# EN-C200_RA0_MCU.net
KiCad netlist of a schematic drawn in Altium Designer
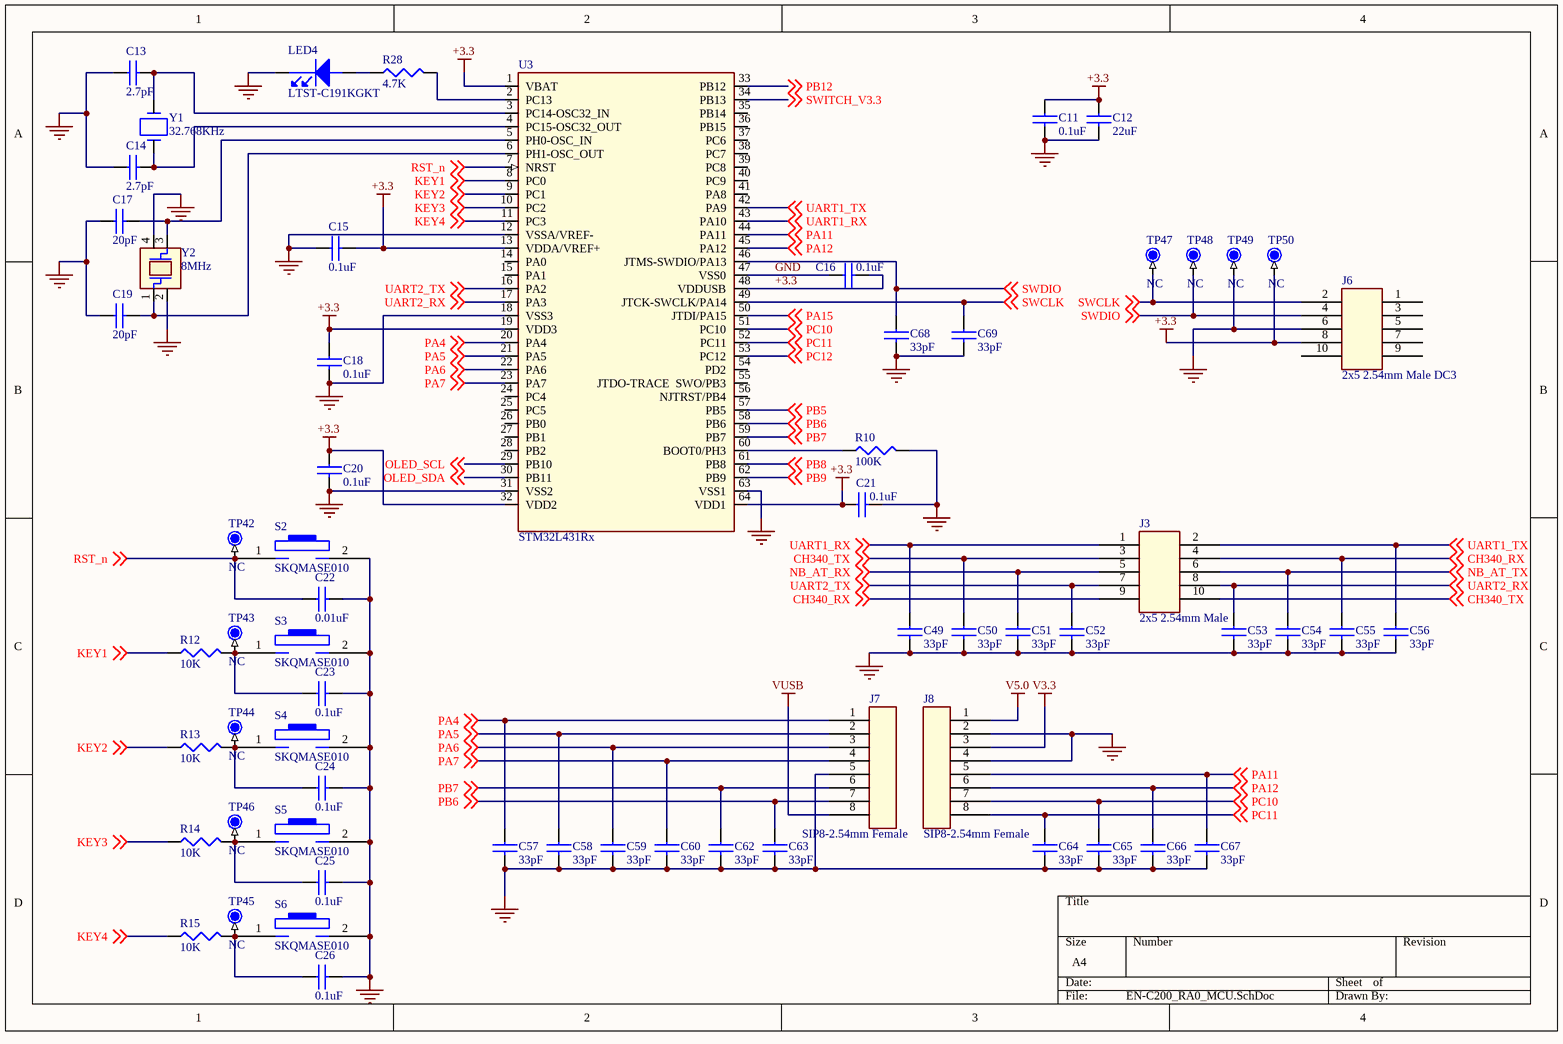
[diagram p0: EN-C200_RA0_MCU.SchDoc]

(export (version "E")
  (design (tool "Eeschema 10.0.6"))
  (components
    (comp (ref "C11") (value "0.1uF") (footprint "SC0603") (libsource (lib "EN-C200_RA0") (part "CAP NP")))
    (comp (ref "C12") (value "22uF") (footprint "SC0805") (libsource (lib "EN-C200_RA0") (part "CAP NP")))
    (comp (ref "C13") (value "2.7pF") (footprint "SC0603") (libsource (lib "EN-C200_RA0") (part "CAP NP")))
    (comp (ref "C14") (value "2.7pF") (footprint "SC0603") (libsource (lib "EN-C200_RA0") (part "CAP NP")))
    (comp (ref "C15") (value "0.1uF") (footprint "SC0603") (libsource (lib "EN-C200_RA0") (part "CAP NP")))
    (comp (ref "C16") (value "0.1uF") (footprint "SC0603") (libsource (lib "EN-C200_RA0") (part "CAP NP")))
    (comp (ref "C17") (value "20pF") (footprint "SC0603") (libsource (lib "EN-C200_RA0") (part "CAP NP")))
    (comp (ref "C18") (value "0.1uF") (footprint "SC0603") (libsource (lib "EN-C200_RA0") (part "CAP NP")))
    (comp (ref "C19") (value "20pF") (footprint "SC0603") (libsource (lib "EN-C200_RA0") (part "CAP NP")))
    (comp (ref "C20") (value "0.1uF") (footprint "SC0603") (libsource (lib "EN-C200_RA0") (part "CAP NP")))
    (comp (ref "C21") (value "0.1uF") (footprint "SC0603") (libsource (lib "EN-C200_RA0") (part "CAP NP")))
    (comp (ref "C22") (value "0.01uF") (footprint "SC0603") (libsource (lib "EN-C200_RA0") (part "CAP NP")))
    (comp (ref "C23") (value "0.1uF") (footprint "SC0603") (libsource (lib "EN-C200_RA0") (part "CAP NP")))
    (comp (ref "C24") (value "0.1uF") (footprint "SC0603") (libsource (lib "EN-C200_RA0") (part "CAP NP")))
    (comp (ref "C25") (value "0.1uF") (footprint "SC0603") (libsource (lib "EN-C200_RA0") (part "CAP NP")))
    (comp (ref "C26") (value "0.1uF") (footprint "SC0603") (libsource (lib "EN-C200_RA0") (part "CAP NP")))
    (comp (ref "C49") (value "33pF") (footprint "SC0603") (libsource (lib "EN-C200_RA0") (part "CAP NP")))
    (comp (ref "C50") (value "33pF") (footprint "SC0603") (libsource (lib "EN-C200_RA0") (part "CAP NP")))
    (comp (ref "C51") (value "33pF") (footprint "SC0603") (libsource (lib "EN-C200_RA0") (part "CAP NP")))
    (comp (ref "C52") (value "33pF") (footprint "SC0603") (libsource (lib "EN-C200_RA0") (part "CAP NP")))
    (comp (ref "C53") (value "33pF") (footprint "SC0603") (libsource (lib "EN-C200_RA0") (part "CAP NP")))
    (comp (ref "C54") (value "33pF") (footprint "SC0603") (libsource (lib "EN-C200_RA0") (part "CAP NP")))
    (comp (ref "C55") (value "33pF") (footprint "SC0603") (libsource (lib "EN-C200_RA0") (part "CAP NP")))
    (comp (ref "C56") (value "33pF") (footprint "SC0603") (libsource (lib "EN-C200_RA0") (part "CAP NP")))
    (comp (ref "C57") (value "33pF") (footprint "SC0603") (libsource (lib "EN-C200_RA0") (part "CAP NP")))
    (comp (ref "C58") (value "33pF") (footprint "SC0603") (libsource (lib "EN-C200_RA0") (part "CAP NP")))
    (comp (ref "C59") (value "33pF") (footprint "SC0603") (libsource (lib "EN-C200_RA0") (part "CAP NP")))
    (comp (ref "C60") (value "33pF") (footprint "SC0603") (libsource (lib "EN-C200_RA0") (part "CAP NP")))
    (comp (ref "C62") (value "33pF") (footprint "SC0603") (libsource (lib "EN-C200_RA0") (part "CAP NP")))
    (comp (ref "C63") (value "33pF") (footprint "SC0603") (libsource (lib "EN-C200_RA0") (part "CAP NP")))
    (comp (ref "C64") (value "33pF") (footprint "SC0603") (libsource (lib "EN-C200_RA0") (part "CAP NP")))
    (comp (ref "C65") (value "33pF") (footprint "SC0603") (libsource (lib "EN-C200_RA0") (part "CAP NP")))
    (comp (ref "C66") (value "33pF") (footprint "SC0603") (libsource (lib "EN-C200_RA0") (part "CAP NP")))
    (comp (ref "C67") (value "33pF") (footprint "SC0603") (libsource (lib "EN-C200_RA0") (part "CAP NP")))
    (comp (ref "C68") (value "33pF") (footprint "SC0603") (libsource (lib "EN-C200_RA0") (part "CAP NP")))
    (comp (ref "C69") (value "33pF") (footprint "SC0603") (libsource (lib "EN-C200_RA0") (part "CAP NP")))
    (comp (ref "J3")
      (value "2x5 2.54mm Male")
      (footprint "SIP-2X5P-100")
      (libsource (lib "EN-C200_RA0") (part "CON10A"))
    )
    (comp (ref "J6")
      (value "2x5 2.54mm Male DC3")
      (footprint "SIP-2X5P-100-DS")
      (libsource (lib "") (part "CON10A_1"))
    )
    (comp (ref "J7")
      (value "SIP8-2.54mm Female")
      (footprint "SIP-8P-100")
      (libsource (lib "EN-C200_RA0") (part "HEADER8"))
    )
    (comp (ref "J8")
      (value "SIP8-2.54mm Female")
      (footprint "SIP-8P-100")
      (libsource (lib "") (part "HEADER8_1"))
    )
    (comp (ref "LED4")
      (value "LTST-C191KGKT")
      (footprint "HSD0603-LED")
      (libsource (lib "EN-C200_RA0") (part "LED"))
    )
    (comp (ref "R10") (value "100K") (footprint "SR0603") (libsource (lib "EN-C200_RA0") (part "RESISTOR")))
    (comp (ref "R12") (value "10K") (footprint "SR0603") (libsource (lib "EN-C200_RA0") (part "RESISTOR")))
    (comp (ref "R13") (value "10K") (footprint "SR0603") (libsource (lib "EN-C200_RA0") (part "RESISTOR")))
    (comp (ref "R14") (value "10K") (footprint "SR0603") (libsource (lib "EN-C200_RA0") (part "RESISTOR")))
    (comp (ref "R15") (value "10K") (footprint "SR0603") (libsource (lib "EN-C200_RA0") (part "RESISTOR")))
    (comp (ref "R28") (value "4.7K") (footprint "SR0603") (libsource (lib "EN-C200_RA0") (part "RESISTOR")))
    (comp (ref "S2")
      (value "SKQMASE010")
      (footprint "SW2-240X140")
      (libsource (lib "EN-C200_RA0") (part "PUSH-KEY"))
    )
    (comp (ref "S3")
      (value "SKQMASE010")
      (footprint "SW2-240X140")
      (libsource (lib "EN-C200_RA0") (part "PUSH-KEY"))
    )
    (comp (ref "S4")
      (value "SKQMASE010")
      (footprint "SW2-240X140")
      (libsource (lib "EN-C200_RA0") (part "PUSH-KEY"))
    )
    (comp (ref "S5")
      (value "SKQMASE010")
      (footprint "SW2-240X140")
      (libsource (lib "EN-C200_RA0") (part "PUSH-KEY"))
    )
    (comp (ref "S6")
      (value "SKQMASE010")
      (footprint "SW2-240X140")
      (libsource (lib "EN-C200_RA0") (part "PUSH-KEY"))
    )
    (comp (ref "TP42") (value "NC") (footprint "TP32-SMD") (libsource (lib "EN-C200_RA0") (part "TP")))
    (comp (ref "TP43") (value "NC") (footprint "TP32-SMD") (libsource (lib "EN-C200_RA0") (part "TP")))
    (comp (ref "TP44") (value "NC") (footprint "TP32-SMD") (libsource (lib "EN-C200_RA0") (part "TP")))
    (comp (ref "TP45") (value "NC") (footprint "TP32-SMD") (libsource (lib "EN-C200_RA0") (part "TP")))
    (comp (ref "TP46") (value "NC") (footprint "TP32-SMD") (libsource (lib "EN-C200_RA0") (part "TP")))
    (comp (ref "TP47") (value "NC") (footprint "TP32-SMD") (libsource (lib "EN-C200_RA0") (part "TP")))
    (comp (ref "TP48") (value "NC") (footprint "TP32-SMD") (libsource (lib "EN-C200_RA0") (part "TP")))
    (comp (ref "TP49") (value "NC") (footprint "TP32-SMD") (libsource (lib "EN-C200_RA0") (part "TP")))
    (comp (ref "TP50") (value "NC") (footprint "TP32-SMD") (libsource (lib "EN-C200_RA0") (part "TP")))
    (comp (ref "U3")
      (value "STM32L431Rx")
      (footprint "QFP64D-050-1010L")
      (libsource (lib "EN-C200_RA0") (part "STM32L431Rx"))
    )
    (comp (ref "Y1")
      (value "32.768KHz")
      (footprint "FC-135_110")
      (libsource (lib "EN-C200_RA0") (part "CRYSTAL2P"))
    )
    (comp (ref "Y2")
      (value "8MHz")
      (footprint "HSX4-0503B")
      (libsource (lib "EN-C200_RA0") (part "CRYSTAL4P"))
    )
  )
  (nets
    (net (code "1") (name "+3.3") (class "Default")
      (node (ref "C11") (pin "1") (pinfunction "1_1") (pintype "passive"))
      (node (ref "C12") (pin "1") (pinfunction "1_1") (pintype "passive"))
      (node (ref "C15") (pin "2") (pinfunction "2_2") (pintype "passive"))
      (node (ref "C16") (pin "2") (pinfunction "2_2") (pintype "passive"))
      (node (ref "C18") (pin "1") (pinfunction "1_1") (pintype "passive"))
      (node (ref "C20") (pin "1") (pinfunction "1_1") (pintype "passive"))
      (node (ref "C21") (pin "1") (pinfunction "1_1") (pintype "passive"))
      (node (ref "J6") (pin "8") (pinfunction "8_8") (pintype "passive"))
      (node (ref "TP50") (pin "1") (pinfunction "1_1") (pintype "input"))
      (node (ref "U3") (pin "1") (pinfunction "VBAT_1") (pintype "power_in"))
      (node (ref "U3") (pin "13") (pinfunction "VDDA/VREF+_13") (pintype "power_in"))
      (node (ref "U3") (pin "19") (pinfunction "VDD3_19") (pintype "power_in"))
      (node (ref "U3") (pin "32") (pinfunction "VDD2_32") (pintype "power_in"))
      (node (ref "U3") (pin "48") (pinfunction "VDDUSB_48") (pintype "power_in"))
      (node (ref "U3") (pin "64") (pinfunction "VDD1_64") (pintype "power_in"))
    )
    (net (code "2") (name "CH340_RX") (class "Default")
      (node (ref "C55") (pin "1") (pinfunction "1_1") (pintype "passive"))
      (node (ref "J3") (pin "4") (pinfunction "4_4") (pintype "passive"))
      (node (ref "J3") (pin "9") (pinfunction "9_9") (pintype "passive"))
    )
    (net (code "3") (name "CH340_TX") (class "Default")
      (node (ref "C50") (pin "1") (pinfunction "1_1") (pintype "passive"))
      (node (ref "J3") (pin "10") (pinfunction "10_10") (pintype "passive"))
      (node (ref "J3") (pin "3") (pinfunction "3_3") (pintype "passive"))
    )
    (net (code "4") (name "GND") (class "Default")
      (node (ref "C11") (pin "2") (pinfunction "2_2") (pintype "passive"))
      (node (ref "C12") (pin "2") (pinfunction "2_2") (pintype "passive"))
      (node (ref "C13") (pin "1") (pinfunction "1_1") (pintype "passive"))
      (node (ref "C14") (pin "1") (pinfunction "1_1") (pintype "passive"))
      (node (ref "C15") (pin "1") (pinfunction "1_1") (pintype "passive"))
      (node (ref "C16") (pin "1") (pinfunction "1_1") (pintype "passive"))
      (node (ref "C17") (pin "1") (pinfunction "1_1") (pintype "passive"))
      (node (ref "C18") (pin "2") (pinfunction "2_2") (pintype "passive"))
      (node (ref "C19") (pin "1") (pinfunction "1_1") (pintype "passive"))
      (node (ref "C20") (pin "2") (pinfunction "2_2") (pintype "passive"))
      (node (ref "C21") (pin "2") (pinfunction "2_2") (pintype "passive"))
      (node (ref "C22") (pin "2") (pinfunction "2_2") (pintype "passive"))
      (node (ref "C23") (pin "2") (pinfunction "2_2") (pintype "passive"))
      (node (ref "C24") (pin "2") (pinfunction "2_2") (pintype "passive"))
      (node (ref "C25") (pin "2") (pinfunction "2_2") (pintype "passive"))
      (node (ref "C26") (pin "2") (pinfunction "2_2") (pintype "passive"))
      (node (ref "C49") (pin "2") (pinfunction "2_2") (pintype "passive"))
      (node (ref "C50") (pin "2") (pinfunction "2_2") (pintype "passive"))
      (node (ref "C51") (pin "2") (pinfunction "2_2") (pintype "passive"))
      (node (ref "C52") (pin "2") (pinfunction "2_2") (pintype "passive"))
      (node (ref "C53") (pin "2") (pinfunction "2_2") (pintype "passive"))
      (node (ref "C54") (pin "2") (pinfunction "2_2") (pintype "passive"))
      (node (ref "C55") (pin "2") (pinfunction "2_2") (pintype "passive"))
      (node (ref "C56") (pin "2") (pinfunction "2_2") (pintype "passive"))
      (node (ref "C57") (pin "2") (pinfunction "2_2") (pintype "passive"))
      (node (ref "C58") (pin "2") (pinfunction "2_2") (pintype "passive"))
      (node (ref "C59") (pin "2") (pinfunction "2_2") (pintype "passive"))
      (node (ref "C60") (pin "2") (pinfunction "2_2") (pintype "passive"))
      (node (ref "C62") (pin "2") (pinfunction "2_2") (pintype "passive"))
      (node (ref "C63") (pin "2") (pinfunction "2_2") (pintype "passive"))
      (node (ref "C64") (pin "2") (pinfunction "2_2") (pintype "passive"))
      (node (ref "C65") (pin "2") (pinfunction "2_2") (pintype "passive"))
      (node (ref "C66") (pin "2") (pinfunction "2_2") (pintype "passive"))
      (node (ref "C67") (pin "2") (pinfunction "2_2") (pintype "passive"))
      (node (ref "C68") (pin "2") (pinfunction "2_2") (pintype "passive"))
      (node (ref "C69") (pin "2") (pinfunction "2_2") (pintype "passive"))
      (node (ref "J6") (pin "6") (pinfunction "6_6") (pintype "passive"))
      (node (ref "J7") (pin "5") (pinfunction "5_5") (pintype "passive"))
      (node (ref "J8") (pin "2") (pinfunction "2_2") (pintype "passive"))
      (node (ref "J8") (pin "4") (pinfunction "4_4") (pintype "passive"))
      (node (ref "LED4") (pin "2") (pinfunction "2_2") (pintype "passive"))
      (node (ref "R10") (pin "2") (pinfunction "2_2") (pintype "passive"))
      (node (ref "S2") (pin "2") (pinfunction "B_2") (pintype "passive"))
      (node (ref "S3") (pin "2") (pinfunction "B_2") (pintype "passive"))
      (node (ref "S4") (pin "2") (pinfunction "B_2") (pintype "passive"))
      (node (ref "S5") (pin "2") (pinfunction "B_2") (pintype "passive"))
      (node (ref "S6") (pin "2") (pinfunction "B_2") (pintype "passive"))
      (node (ref "TP49") (pin "1") (pinfunction "1_1") (pintype "input"))
      (node (ref "U3") (pin "12") (pinfunction "VSSA/VREF-_12") (pintype "power_in"))
      (node (ref "U3") (pin "18") (pinfunction "VSS3_18") (pintype "power_in"))
      (node (ref "U3") (pin "31") (pinfunction "VSS2_31") (pintype "power_in"))
      (node (ref "U3") (pin "47") (pinfunction "VSS0_47") (pintype "power_in"))
      (node (ref "U3") (pin "63") (pinfunction "VSS1_63") (pintype "power_in"))
      (node (ref "Y2") (pin "2") (pinfunction "2_2") (pintype "passive"))
      (node (ref "Y2") (pin "4") (pinfunction "4_4") (pintype "passive"))
    )
    (net (code "5") (name "KEY1") (class "Default")
      (node (ref "R12") (pin "1") (pinfunction "1_1") (pintype "passive"))
      (node (ref "U3") (pin "8") (pinfunction "PC0_8") (pintype "bidirectional"))
    )
    (net (code "6") (name "KEY2") (class "Default")
      (node (ref "R13") (pin "1") (pinfunction "1_1") (pintype "passive"))
      (node (ref "U3") (pin "9") (pinfunction "PC1_9") (pintype "bidirectional"))
    )
    (net (code "7") (name "KEY3") (class "Default")
      (node (ref "R14") (pin "1") (pinfunction "1_1") (pintype "passive"))
      (node (ref "U3") (pin "10") (pinfunction "PC2_10") (pintype "bidirectional"))
    )
    (net (code "8") (name "KEY4") (class "Default")
      (node (ref "R15") (pin "1") (pinfunction "1_1") (pintype "passive"))
      (node (ref "U3") (pin "11") (pinfunction "PC3_11") (pintype "bidirectional"))
    )
    (net (code "9") (name "NB_AT_RX") (class "Default")
      (node (ref "C51") (pin "1") (pinfunction "1_1") (pintype "passive"))
      (node (ref "J3") (pin "5") (pinfunction "5_5") (pintype "passive"))
    )
    (net (code "10") (name "NB_AT_TX") (class "Default")
      (node (ref "C54") (pin "1") (pinfunction "1_1") (pintype "passive"))
      (node (ref "J3") (pin "6") (pinfunction "6_6") (pintype "passive"))
    )
    (net (code "11") (name "Net-(LED4-Pad1)") (class "Default")
      (node (ref "LED4") (pin "1") (pinfunction "1_1") (pintype "passive"))
      (node (ref "R28") (pin "1") (pinfunction "1_1") (pintype "passive"))
    )
    (net (code "12") (name "Net-(S3-A)") (class "Default")
      (node (ref "C23") (pin "1") (pinfunction "1_1") (pintype "passive"))
      (node (ref "R12") (pin "2") (pinfunction "2_2") (pintype "passive"))
      (node (ref "S3") (pin "1") (pinfunction "A_1") (pintype "passive"))
      (node (ref "TP43") (pin "1") (pinfunction "1_1") (pintype "input"))
    )
    (net (code "13") (name "Net-(S4-A)") (class "Default")
      (node (ref "C24") (pin "1") (pinfunction "1_1") (pintype "passive"))
      (node (ref "R13") (pin "2") (pinfunction "2_2") (pintype "passive"))
      (node (ref "S4") (pin "1") (pinfunction "A_1") (pintype "passive"))
      (node (ref "TP44") (pin "1") (pinfunction "1_1") (pintype "input"))
    )
    (net (code "14") (name "Net-(S5-A)") (class "Default")
      (node (ref "C25") (pin "1") (pinfunction "1_1") (pintype "passive"))
      (node (ref "R14") (pin "2") (pinfunction "2_2") (pintype "passive"))
      (node (ref "S5") (pin "1") (pinfunction "A_1") (pintype "passive"))
      (node (ref "TP46") (pin "1") (pinfunction "1_1") (pintype "input"))
    )
    (net (code "15") (name "Net-(S6-A)") (class "Default")
      (node (ref "C26") (pin "1") (pinfunction "1_1") (pintype "passive"))
      (node (ref "R15") (pin "2") (pinfunction "2_2") (pintype "passive"))
      (node (ref "S6") (pin "1") (pinfunction "A_1") (pintype "passive"))
      (node (ref "TP45") (pin "1") (pinfunction "1_1") (pintype "input"))
    )
    (net (code "16") (name "Net-(U3-BOOT0{slash}PH3)") (class "Default")
      (node (ref "R10") (pin "1") (pinfunction "1_1") (pintype "passive"))
      (node (ref "U3") (pin "60") (pinfunction "BOOT0/PH3_60") (pintype "bidirectional"))
    )
    (net (code "17") (name "Net-(U3-PC13)") (class "Default")
      (node (ref "R28") (pin "2") (pinfunction "2_2") (pintype "passive"))
      (node (ref "U3") (pin "2") (pinfunction "PC13_2") (pintype "bidirectional"))
    )
    (net (code "18") (name "Net-(U3-PC14-OSC32_IN)") (class "Default")
      (node (ref "C13") (pin "2") (pinfunction "2_2") (pintype "passive"))
      (node (ref "U3") (pin "3") (pinfunction "PC14-OSC32_IN_3") (pintype "bidirectional"))
      (node (ref "Y1") (pin "2") (pinfunction "2_2") (pintype "passive"))
    )
    (net (code "19") (name "Net-(U3-PC15-OSC32_OUT)") (class "Default")
      (node (ref "C14") (pin "2") (pinfunction "2_2") (pintype "passive"))
      (node (ref "U3") (pin "4") (pinfunction "PC15-OSC32_OUT_4") (pintype "bidirectional"))
      (node (ref "Y1") (pin "1") (pinfunction "1_1") (pintype "passive"))
    )
    (net (code "20") (name "Net-(U3-PH0-OSC_IN)") (class "Default")
      (node (ref "C17") (pin "2") (pinfunction "2_2") (pintype "passive"))
      (node (ref "U3") (pin "5") (pinfunction "PH0-OSC_IN_5") (pintype "bidirectional"))
      (node (ref "Y2") (pin "3") (pinfunction "COUT_3") (pintype "passive"))
    )
    (net (code "21") (name "Net-(U3-PH1-OSC_OUT)") (class "Default")
      (node (ref "C19") (pin "2") (pinfunction "2_2") (pintype "passive"))
      (node (ref "U3") (pin "6") (pinfunction "PH1-OSC_OUT_6") (pintype "bidirectional"))
      (node (ref "Y2") (pin "1") (pinfunction "CIN_1") (pintype "passive"))
    )
    (net (code "22") (name "OLED_SCL") (class "Default")
      (node (ref "U3") (pin "29") (pinfunction "PB10_29") (pintype "bidirectional"))
    )
    (net (code "23") (name "OLED_SDA") (class "Default")
      (node (ref "U3") (pin "30") (pinfunction "PB11_30") (pintype "bidirectional"))
    )
    (net (code "24") (name "PA4") (class "Default")
      (node (ref "C57") (pin "1") (pinfunction "1_1") (pintype "passive"))
      (node (ref "J7") (pin "1") (pinfunction "1_1") (pintype "passive"))
      (node (ref "U3") (pin "20") (pinfunction "PA4_20") (pintype "bidirectional"))
    )
    (net (code "25") (name "PA5") (class "Default")
      (node (ref "C58") (pin "1") (pinfunction "1_1") (pintype "passive"))
      (node (ref "J7") (pin "2") (pinfunction "2_2") (pintype "passive"))
      (node (ref "U3") (pin "21") (pinfunction "PA5_21") (pintype "bidirectional"))
    )
    (net (code "26") (name "PA6") (class "Default")
      (node (ref "C59") (pin "1") (pinfunction "1_1") (pintype "passive"))
      (node (ref "J7") (pin "3") (pinfunction "3_3") (pintype "passive"))
      (node (ref "U3") (pin "22") (pinfunction "PA6_22") (pintype "bidirectional"))
    )
    (net (code "27") (name "PA7") (class "Default")
      (node (ref "C60") (pin "1") (pinfunction "1_1") (pintype "passive"))
      (node (ref "J7") (pin "4") (pinfunction "4_4") (pintype "passive"))
      (node (ref "U3") (pin "23") (pinfunction "PA7_23") (pintype "bidirectional"))
    )
    (net (code "28") (name "PA11") (class "Default")
      (node (ref "C67") (pin "1") (pinfunction "1_1") (pintype "passive"))
      (node (ref "J8") (pin "5") (pinfunction "5_5") (pintype "passive"))
      (node (ref "U3") (pin "44") (pinfunction "PA11_44") (pintype "bidirectional"))
    )
    (net (code "29") (name "PA12") (class "Default")
      (node (ref "C66") (pin "1") (pinfunction "1_1") (pintype "passive"))
      (node (ref "J8") (pin "6") (pinfunction "6_6") (pintype "passive"))
      (node (ref "U3") (pin "45") (pinfunction "PA12_45") (pintype "bidirectional"))
    )
    (net (code "30") (name "PA15") (class "Default")
      (node (ref "U3") (pin "50") (pinfunction "JTDI/PA15_50") (pintype "bidirectional"))
    )
    (net (code "31") (name "PB5") (class "Default")
      (node (ref "U3") (pin "57") (pinfunction "PB5_57") (pintype "bidirectional"))
    )
    (net (code "32") (name "PB6") (class "Default")
      (node (ref "C63") (pin "1") (pinfunction "1_1") (pintype "passive"))
      (node (ref "J7") (pin "7") (pinfunction "7_7") (pintype "passive"))
      (node (ref "U3") (pin "58") (pinfunction "PB6_58") (pintype "bidirectional"))
    )
    (net (code "33") (name "PB7") (class "Default")
      (node (ref "C62") (pin "1") (pinfunction "1_1") (pintype "passive"))
      (node (ref "J7") (pin "6") (pinfunction "6_6") (pintype "passive"))
      (node (ref "U3") (pin "59") (pinfunction "PB7_59") (pintype "bidirectional"))
    )
    (net (code "34") (name "PB8") (class "Default")
      (node (ref "U3") (pin "61") (pinfunction "PB8_61") (pintype "bidirectional"))
    )
    (net (code "35") (name "PB9") (class "Default")
      (node (ref "U3") (pin "62") (pinfunction "PB9_62") (pintype "bidirectional"))
    )
    (net (code "36") (name "PB12") (class "Default")
      (node (ref "U3") (pin "33") (pinfunction "PB12_33") (pintype "bidirectional"))
    )
    (net (code "37") (name "PC10") (class "Default")
      (node (ref "C65") (pin "1") (pinfunction "1_1") (pintype "passive"))
      (node (ref "J8") (pin "7") (pinfunction "7_7") (pintype "passive"))
      (node (ref "U3") (pin "51") (pinfunction "PC10_51") (pintype "bidirectional"))
    )
    (net (code "38") (name "PC11") (class "Default")
      (node (ref "C64") (pin "1") (pinfunction "1_1") (pintype "passive"))
      (node (ref "J8") (pin "8") (pinfunction "8_8") (pintype "passive"))
      (node (ref "U3") (pin "52") (pinfunction "PC11_52") (pintype "bidirectional"))
    )
    (net (code "39") (name "PC12") (class "Default")
      (node (ref "U3") (pin "53") (pinfunction "PC12_53") (pintype "bidirectional"))
    )
    (net (code "40") (name "RST_n") (class "Default")
      (node (ref "C22") (pin "1") (pinfunction "1_1") (pintype "passive"))
      (node (ref "S2") (pin "1") (pinfunction "A_1") (pintype "passive"))
      (node (ref "TP42") (pin "1") (pinfunction "1_1") (pintype "input"))
      (node (ref "U3") (pin "7") (pinfunction "NRST_7") (pintype "input"))
    )
    (net (code "41") (name "SWCLK") (class "Default")
      (node (ref "C69") (pin "1") (pinfunction "1_1") (pintype "passive"))
      (node (ref "J6") (pin "2") (pinfunction "2_2") (pintype "passive"))
      (node (ref "TP47") (pin "1") (pinfunction "1_1") (pintype "input"))
      (node (ref "U3") (pin "49") (pinfunction "JTCK-SWCLK/PA14_49") (pintype "bidirectional"))
    )
    (net (code "42") (name "SWDIO") (class "Default")
      (node (ref "C68") (pin "1") (pinfunction "1_1") (pintype "passive"))
      (node (ref "J6") (pin "4") (pinfunction "4_4") (pintype "passive"))
      (node (ref "TP48") (pin "1") (pinfunction "1_1") (pintype "input"))
      (node (ref "U3") (pin "46") (pinfunction "JTMS-SWDIO/PA13_46") (pintype "bidirectional"))
    )
    (net (code "43") (name "SWITCH_V3.3") (class "Default")
      (node (ref "U3") (pin "34") (pinfunction "PB13_34") (pintype "bidirectional"))
    )
    (net (code "44") (name "UART1_RX") (class "Default")
      (node (ref "C49") (pin "1") (pinfunction "1_1") (pintype "passive"))
      (node (ref "J3") (pin "1") (pinfunction "1_1") (pintype "passive"))
      (node (ref "U3") (pin "43") (pinfunction "PA10_43") (pintype "bidirectional"))
    )
    (net (code "45") (name "UART1_TX") (class "Default")
      (node (ref "C56") (pin "1") (pinfunction "1_1") (pintype "passive"))
      (node (ref "J3") (pin "2") (pinfunction "2_2") (pintype "passive"))
      (node (ref "U3") (pin "42") (pinfunction "PA9_42") (pintype "bidirectional"))
    )
    (net (code "46") (name "UART2_RX") (class "Default")
      (node (ref "C53") (pin "1") (pinfunction "1_1") (pintype "passive"))
      (node (ref "J3") (pin "8") (pinfunction "8_8") (pintype "passive"))
      (node (ref "U3") (pin "17") (pinfunction "PA3_17") (pintype "bidirectional"))
    )
    (net (code "47") (name "UART2_TX") (class "Default")
      (node (ref "C52") (pin "1") (pinfunction "1_1") (pintype "passive"))
      (node (ref "J3") (pin "7") (pinfunction "7_7") (pintype "passive"))
      (node (ref "U3") (pin "16") (pinfunction "PA2_16") (pintype "bidirectional"))
    )
    (net (code "48") (name "V3.3") (class "Default")
      (node (ref "J8") (pin "3") (pinfunction "3_3") (pintype "passive"))
    )
    (net (code "49") (name "V5.0") (class "Default")
      (node (ref "J8") (pin "1") (pinfunction "1_1") (pintype "passive"))
    )
    (net (code "50") (name "VUSB") (class "Default")
      (node (ref "J7") (pin "8") (pinfunction "8_8") (pintype "passive"))
    )
    (net (code "51") (name "unconnected-(J6-Pad1)") (class "Default")
      (node (ref "J6") (pin "1") (pinfunction "1_1") (pintype "passive"))
    )
    (net (code "52") (name "unconnected-(J6-Pad3)") (class "Default")
      (node (ref "J6") (pin "3") (pinfunction "3_3") (pintype "passive"))
    )
    (net (code "53") (name "unconnected-(J6-Pad5)") (class "Default")
      (node (ref "J6") (pin "5") (pinfunction "5_5") (pintype "passive"))
    )
    (net (code "54") (name "unconnected-(J6-Pad7)") (class "Default")
      (node (ref "J6") (pin "7") (pinfunction "7_7") (pintype "passive"))
    )
    (net (code "55") (name "unconnected-(J6-Pad9)") (class "Default")
      (node (ref "J6") (pin "9") (pinfunction "9_9") (pintype "passive"))
    )
    (net (code "56") (name "unconnected-(J6-Pad10)") (class "Default")
      (node (ref "J6") (pin "10") (pinfunction "10_10") (pintype "passive"))
    )
    (net (code "57") (name "unconnected-(U3-JTDO-TRACE__SWO{slash}PB3-Pad55)") (class "Default")
      (node (ref "U3") (pin "55") (pinfunction "JTDO-TRACE__SWO/PB3_55") (pintype "bidirectional"))
    )
    (net (code "58") (name "unconnected-(U3-NJTRST{slash}PB4-Pad56)") (class "Default")
      (node (ref "U3") (pin "56") (pinfunction "NJTRST/PB4_56") (pintype "bidirectional"))
    )
    (net (code "59") (name "unconnected-(U3-PA0-Pad14)") (class "Default")
      (node (ref "U3") (pin "14") (pinfunction "PA0_14") (pintype "bidirectional"))
    )
    (net (code "60") (name "unconnected-(U3-PA1-Pad15)") (class "Default")
      (node (ref "U3") (pin "15") (pinfunction "PA1_15") (pintype "bidirectional"))
    )
    (net (code "61") (name "unconnected-(U3-PA8-Pad41)") (class "Default")
      (node (ref "U3") (pin "41") (pinfunction "PA8_41") (pintype "bidirectional"))
    )
    (net (code "62") (name "unconnected-(U3-PB0-Pad26)") (class "Default")
      (node (ref "U3") (pin "26") (pinfunction "PB0_26") (pintype "bidirectional"))
    )
    (net (code "63") (name "unconnected-(U3-PB1-Pad27)") (class "Default")
      (node (ref "U3") (pin "27") (pinfunction "PB1_27") (pintype "bidirectional"))
    )
    (net (code "64") (name "unconnected-(U3-PB2-Pad28)") (class "Default")
      (node (ref "U3") (pin "28") (pinfunction "PB2_28") (pintype "bidirectional"))
    )
    (net (code "65") (name "unconnected-(U3-PB14-Pad35)") (class "Default")
      (node (ref "U3") (pin "35") (pinfunction "PB14_35") (pintype "bidirectional"))
    )
    (net (code "66") (name "unconnected-(U3-PB15-Pad36)") (class "Default")
      (node (ref "U3") (pin "36") (pinfunction "PB15_36") (pintype "bidirectional"))
    )
    (net (code "67") (name "unconnected-(U3-PC4-Pad24)") (class "Default")
      (node (ref "U3") (pin "24") (pinfunction "PC4_24") (pintype "bidirectional"))
    )
    (net (code "68") (name "unconnected-(U3-PC5-Pad25)") (class "Default")
      (node (ref "U3") (pin "25") (pinfunction "PC5_25") (pintype "bidirectional"))
    )
    (net (code "69") (name "unconnected-(U3-PC6-Pad37)") (class "Default")
      (node (ref "U3") (pin "37") (pinfunction "PC6_37") (pintype "bidirectional"))
    )
    (net (code "70") (name "unconnected-(U3-PC7-Pad38)") (class "Default")
      (node (ref "U3") (pin "38") (pinfunction "PC7_38") (pintype "bidirectional"))
    )
    (net (code "71") (name "unconnected-(U3-PC8-Pad39)") (class "Default")
      (node (ref "U3") (pin "39") (pinfunction "PC8_39") (pintype "bidirectional"))
    )
    (net (code "72") (name "unconnected-(U3-PC9-Pad40)") (class "Default")
      (node (ref "U3") (pin "40") (pinfunction "PC9_40") (pintype "bidirectional"))
    )
    (net (code "73") (name "unconnected-(U3-PD2-Pad54)") (class "Default")
      (node (ref "U3") (pin "54") (pinfunction "PD2_54") (pintype "bidirectional"))
    )
  )
)
